# Sensors.net
KiCad netlist of a schematic drawn in Altium Designer
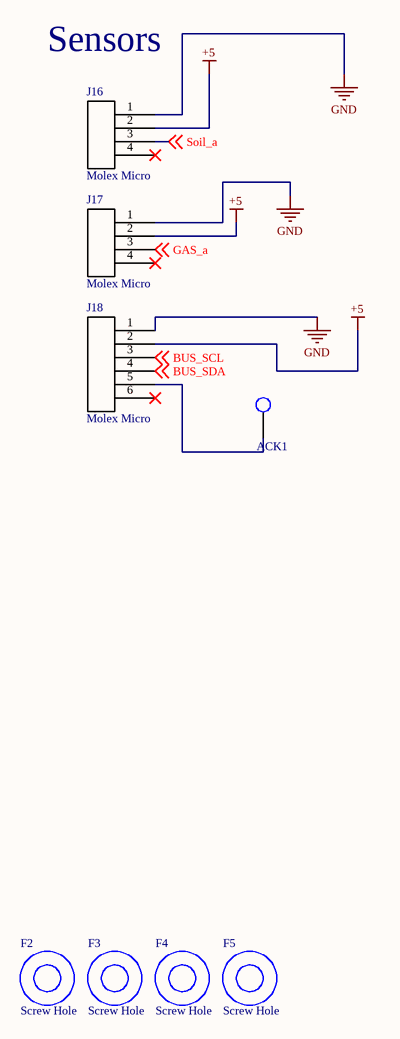
[diagram p0: Sensors.SchDoc]

(export (version "E")
  (design (tool "Eeschema 10.0.6"))
  (components
    (comp (ref "ACK1")
      (value "Test Point")
      (footprint "Test Point Through-hole")
      (libsource (lib "Husky Robotics Standard Library 2019-2020") (part "Test Point"))
    )
    (comp (ref "F2")
      (value "Screw Hole")
      (footprint "Screw Hole")
      (description "Add 4 of these to your design for screw hole mounting")
      (libsource (lib "Husky Robotics Standard Library 2019-2020") (part "Screw Hole"))
    )
    (comp (ref "F3")
      (value "Screw Hole")
      (footprint "Screw Hole")
      (description "Add 4 of these to your design for screw hole mounting")
      (libsource (lib "Husky Robotics Standard Library 2019-2020") (part "Screw Hole"))
    )
    (comp (ref "F4")
      (value "Screw Hole")
      (footprint "Screw Hole")
      (description "Add 4 of these to your design for screw hole mounting")
      (libsource (lib "Husky Robotics Standard Library 2019-2020") (part "Screw Hole"))
    )
    (comp (ref "F5")
      (value "Screw Hole")
      (footprint "Screw Hole")
      (description "Add 4 of these to your design for screw hole mounting")
      (libsource (lib "Husky Robotics Standard Library 2019-2020") (part "Screw Hole"))
    )
    (comp (ref "J16")
      (value "Molex Micro")
      (footprint "MICROFIT R/A 4 PIN")
      (description "Molex micro-fit 3.0 dual row header. P/N 0430450427")
      (libsource (lib "Husky Robotics Standard Library 2019-2020") (part "Molex micro-fit 4-pin (Single row schematic)"))
    )
    (comp (ref "J17")
      (value "Molex Micro")
      (footprint "MICROFIT R/A 4 PIN")
      (description "Molex micro-fit 3.0 dual row header. P/N 0430450427")
      (libsource (lib "Husky Robotics Standard Library 2019-2020") (part "Molex micro-fit 4-pin (Single row schematic)"))
    )
    (comp (ref "J18")
      (value "Molex Micro")
      (footprint "MICROFIT R/A 6 PIN")
      (description "Molex micro-fit 3.0 dual row connector. P/N 0430450627")
      (libsource (lib "Husky Robotics Standard Library 2019-2020") (part "Molex micro-fit 6-pin (single row schematic)"))
    )
  )
  (nets
    (net (code "1") (name "+5") (class "Default")
      (node (ref "J16") (pin "2") (pintype "passive"))
      (node (ref "J17") (pin "2") (pintype "passive"))
      (node (ref "J18") (pin "2") (pintype "passive"))
    )
    (net (code "2") (name "BUS_SCL") (class "Default") (node (ref "J18") (pin "3") (pintype "passive")))
    (net (code "3") (name "BUS_SDA") (class "Default") (node (ref "J18") (pin "4") (pintype "passive")))
    (net (code "4") (name "GAS_a") (class "Default") (node (ref "J17") (pin "3") (pintype "passive")))
    (net (code "5") (name "GND") (class "Default")
      (node (ref "J16") (pin "1") (pintype "passive"))
      (node (ref "J17") (pin "1") (pintype "passive"))
      (node (ref "J18") (pin "1") (pintype "passive"))
    )
    (net (code "6") (name "Net-(ACK1-Pad1)") (class "Default")
      (node (ref "ACK1") (pin "1") (pinfunction "1_1") (pintype "passive"))
      (node (ref "J18") (pin "5") (pintype "passive"))
    )
    (net (code "7") (name "Soil_a") (class "Default") (node (ref "J16") (pin "3") (pintype "passive")))
    (net (code "8") (name "unconnected-(J16-Pad4)") (class "Default")
      (node (ref "J16") (pin "4") (pintype "passive+no_connect"))
    )
    (net (code "9") (name "unconnected-(J17-Pad4)") (class "Default")
      (node (ref "J17") (pin "4") (pintype "passive+no_connect"))
    )
    (net (code "10") (name "unconnected-(J18-Pad6)") (class "Default")
      (node (ref "J18") (pin "6") (pintype "passive+no_connect"))
    )
  )
)
